# ICEBoard_rev1_0.net
KiCad netlist of a schematic drawn in Altium Designer
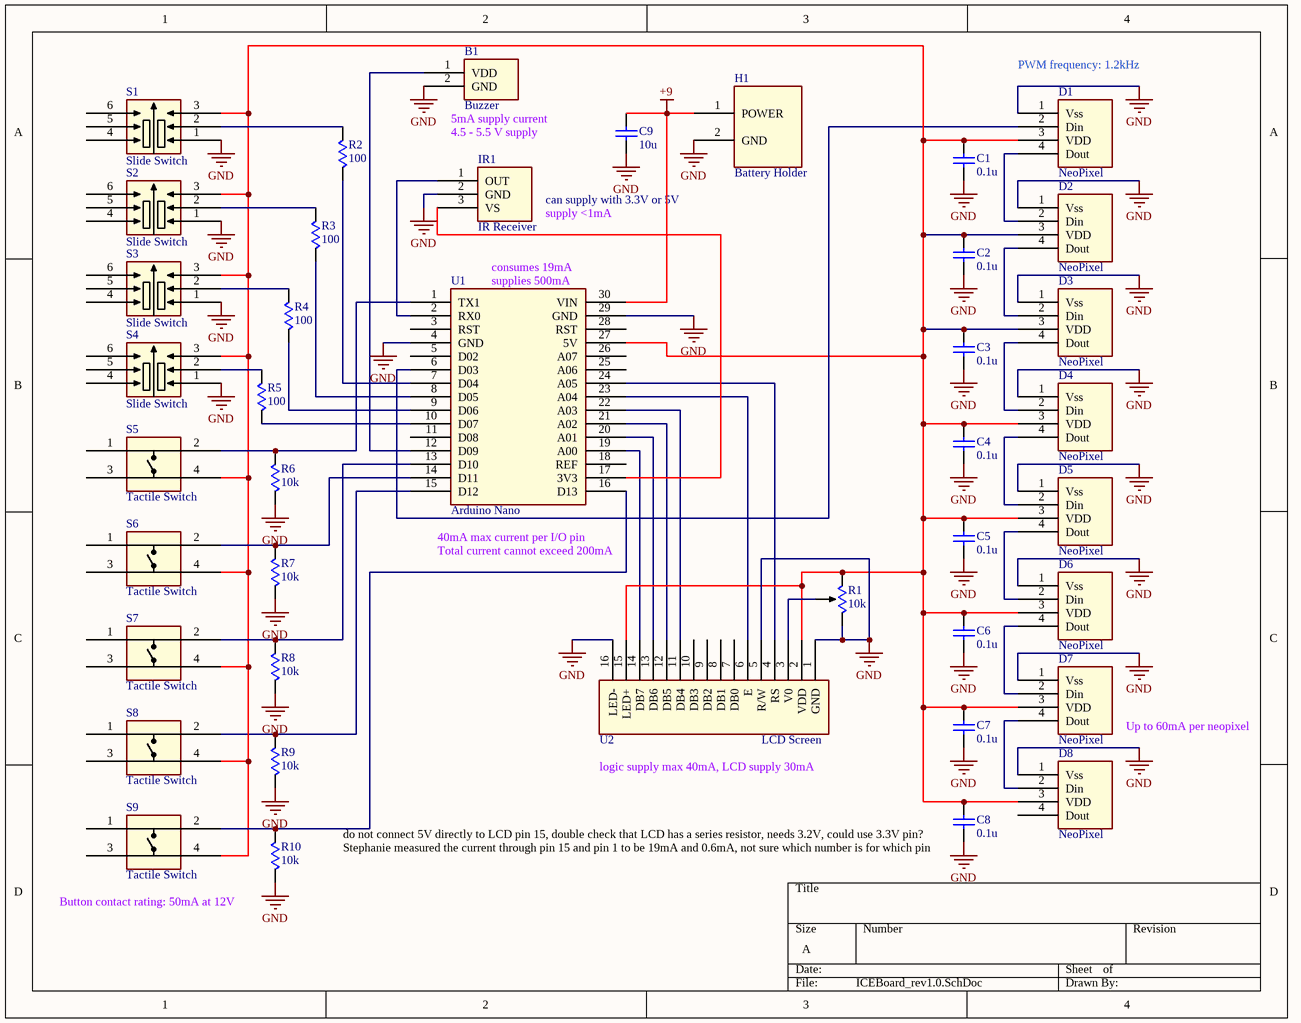
[diagram p0: ICEBoard_rev1.0.SchDoc]

(export (version "E")
  (design (tool "Eeschema 10.0.6"))
  (components
    (comp (ref "B1") (value "Buzzer") (footprint "TP124005") (libsource (lib "TP124005") (part "TP124005")))
    (comp (ref "C1") (value "0.1u") (footprint "Capacitor") (libsource (lib "Capacitor") (part "Capacitor")))
    (comp (ref "C2") (value "0.1u") (footprint "Capacitor") (libsource (lib "Capacitor") (part "Capacitor")))
    (comp (ref "C3") (value "0.1u") (footprint "Capacitor") (libsource (lib "Capacitor") (part "Capacitor")))
    (comp (ref "C4") (value "0.1u") (footprint "Capacitor") (libsource (lib "Capacitor") (part "Capacitor")))
    (comp (ref "C5") (value "0.1u") (footprint "Capacitor") (libsource (lib "Capacitor") (part "Capacitor")))
    (comp (ref "C6") (value "0.1u") (footprint "Capacitor") (libsource (lib "Capacitor") (part "Capacitor")))
    (comp (ref "C7") (value "0.1u") (footprint "Capacitor") (libsource (lib "Capacitor") (part "Capacitor")))
    (comp (ref "C8") (value "0.1u") (footprint "Capacitor") (libsource (lib "Capacitor") (part "Capacitor")))
    (comp (ref "C9")
      (value "10u")
      (footprint "PCBComponent_1")
      (libsource (lib "Capacitor") (part "Capacitor"))
    )
    (comp (ref "D1") (value "NeoPixel") (footprint "NeoPixel") (libsource (lib "NeoPixel") (part "NeoPixel")))
    (comp (ref "D2") (value "NeoPixel") (footprint "NeoPixel") (libsource (lib "NeoPixel") (part "NeoPixel")))
    (comp (ref "D3") (value "NeoPixel") (footprint "NeoPixel") (libsource (lib "NeoPixel") (part "NeoPixel")))
    (comp (ref "D4") (value "NeoPixel") (footprint "NeoPixel") (libsource (lib "NeoPixel") (part "NeoPixel")))
    (comp (ref "D5") (value "NeoPixel") (footprint "NeoPixel") (libsource (lib "NeoPixel") (part "NeoPixel")))
    (comp (ref "D6") (value "NeoPixel") (footprint "NeoPixel") (libsource (lib "NeoPixel") (part "NeoPixel")))
    (comp (ref "D7") (value "NeoPixel") (footprint "NeoPixel") (libsource (lib "NeoPixel") (part "NeoPixel")))
    (comp (ref "D8") (value "NeoPixel") (footprint "NeoPixel") (libsource (lib "NeoPixel") (part "NeoPixel")))
    (comp (ref "H1") (value "Battery Holder") (footprint "BH9VPC") (libsource (lib "BH9VPC") (part "BH9VPC")))
    (comp (ref "IR1")
      (value "IR Receiver")
      (footprint "TSOP382")
      (libsource (lib "TSOP382") (part "TSOP382"))
    )
    (comp (ref "R1")
      (value "10k")
      (footprint "TC33X")
      (libsource (lib "Resistor - Variable") (part "Resistor - Variable"))
    )
    (comp (ref "R2") (value "100") (footprint "Resistor1608") (libsource (lib "Resistor") (part "Resistor")))
    (comp (ref "R3") (value "100") (footprint "Resistor1608") (libsource (lib "Resistor") (part "Resistor")))
    (comp (ref "R4") (value "100") (footprint "Resistor1608") (libsource (lib "Resistor") (part "Resistor")))
    (comp (ref "R5") (value "100") (footprint "Resistor1608") (libsource (lib "Resistor") (part "Resistor")))
    (comp (ref "R6") (value "10k") (footprint "Resistor1608") (libsource (lib "Resistor") (part "Resistor")))
    (comp (ref "R7") (value "10k") (footprint "Resistor1608") (libsource (lib "Resistor") (part "Resistor")))
    (comp (ref "R8") (value "10k") (footprint "Resistor1608") (libsource (lib "Resistor") (part "Resistor")))
    (comp (ref "R9") (value "10k") (footprint "Resistor1608") (libsource (lib "Resistor") (part "Resistor")))
    (comp (ref "R10") (value "10k") (footprint "Resistor1608") (libsource (lib "Resistor") (part "Resistor")))
    (comp (ref "S1")
      (value "Slide Switch")
      (footprint "JS202011SCQN")
      (libsource (lib "JS202011SCQN") (part "JS202011SCQN"))
    )
    (comp (ref "S2")
      (value "Slide Switch")
      (footprint "JS202011SCQN")
      (libsource (lib "JS202011SCQN") (part "JS202011SCQN"))
    )
    (comp (ref "S3")
      (value "Slide Switch")
      (footprint "JS202011SCQN")
      (libsource (lib "JS202011SCQN") (part "JS202011SCQN"))
    )
    (comp (ref "S4")
      (value "Slide Switch")
      (footprint "JS202011SCQN")
      (libsource (lib "JS202011SCQN") (part "JS202011SCQN"))
    )
    (comp (ref "S5") (value "Tactile Switch") (footprint "PTS645") (libsource (lib "PTS645") (part "PTS645")))
    (comp (ref "S6") (value "Tactile Switch") (footprint "PTS645") (libsource (lib "PTS645") (part "PTS645")))
    (comp (ref "S7") (value "Tactile Switch") (footprint "PTS645") (libsource (lib "PTS645") (part "PTS645")))
    (comp (ref "S8") (value "Tactile Switch") (footprint "PTS645") (libsource (lib "PTS645") (part "PTS645")))
    (comp (ref "S9") (value "Tactile Switch") (footprint "PTS645") (libsource (lib "PTS645") (part "PTS645")))
    (comp (ref "U1")
      (value "Arduino Nano")
      (footprint "ArduinoNano")
      (libsource (lib "ArduinoNano") (part "ArduinoNano"))
    )
    (comp (ref "U2")
      (value "LCD Screen")
      (footprint "TC1602A-01T")
      (libsource (lib "TC1602A-01T") (part "TC1602A-01T"))
    )
  )
  (nets
    (net (code "1") (name "+9") (class "Default")
      (node (ref "C9") (pin "1") (pinfunction "1_1") (pintype "passive"))
      (node (ref "H1") (pin "1") (pinfunction "POWER_1") (pintype "passive"))
      (node (ref "U1") (pin "30") (pinfunction "VIN_30") (pintype "passive"))
    )
    (net (code "2") (name "GND") (class "Default")
      (node (ref "B1") (pin "2") (pinfunction "GND_2") (pintype "passive"))
      (node (ref "C1") (pin "2") (pinfunction "2_2") (pintype "passive"))
      (node (ref "C2") (pin "2") (pinfunction "2_2") (pintype "passive"))
      (node (ref "C3") (pin "2") (pinfunction "2_2") (pintype "passive"))
      (node (ref "C4") (pin "2") (pinfunction "2_2") (pintype "passive"))
      (node (ref "C5") (pin "2") (pinfunction "2_2") (pintype "passive"))
      (node (ref "C6") (pin "2") (pinfunction "2_2") (pintype "passive"))
      (node (ref "C7") (pin "2") (pinfunction "2_2") (pintype "passive"))
      (node (ref "C8") (pin "2") (pinfunction "2_2") (pintype "passive"))
      (node (ref "C9") (pin "2") (pinfunction "2_2") (pintype "passive"))
      (node (ref "D1") (pin "1") (pinfunction "Vss_1") (pintype "passive"))
      (node (ref "D2") (pin "1") (pinfunction "Vss_1") (pintype "passive"))
      (node (ref "D3") (pin "1") (pinfunction "Vss_1") (pintype "passive"))
      (node (ref "D4") (pin "1") (pinfunction "Vss_1") (pintype "passive"))
      (node (ref "D5") (pin "1") (pinfunction "Vss_1") (pintype "passive"))
      (node (ref "D6") (pin "1") (pinfunction "Vss_1") (pintype "passive"))
      (node (ref "D7") (pin "1") (pinfunction "Vss_1") (pintype "passive"))
      (node (ref "D8") (pin "1") (pinfunction "Vss_1") (pintype "passive"))
      (node (ref "H1") (pin "2") (pinfunction "GND_2") (pintype "passive"))
      (node (ref "IR1") (pin "2") (pinfunction "GND_2") (pintype "passive"))
      (node (ref "R1") (pin "1") (pinfunction "1_1") (pintype "passive"))
      (node (ref "R10") (pin "1") (pinfunction "1_1") (pintype "passive"))
      (node (ref "R6") (pin "1") (pinfunction "1_1") (pintype "passive"))
      (node (ref "R7") (pin "1") (pinfunction "1_1") (pintype "passive"))
      (node (ref "R8") (pin "1") (pinfunction "1_1") (pintype "passive"))
      (node (ref "R9") (pin "1") (pinfunction "1_1") (pintype "passive"))
      (node (ref "S1") (pin "1") (pintype "passive"))
      (node (ref "S2") (pin "1") (pintype "passive"))
      (node (ref "S3") (pin "1") (pintype "passive"))
      (node (ref "S4") (pin "1") (pintype "passive"))
      (node (ref "U1") (pin "29") (pinfunction "GND_29") (pintype "passive"))
      (node (ref "U1") (pin "4") (pinfunction "GND_4") (pintype "passive"))
      (node (ref "U2") (pin "1") (pinfunction "GND_1") (pintype "passive"))
      (node (ref "U2") (pin "16") (pinfunction "LED-_16") (pintype "passive"))
      (node (ref "U2") (pin "5") (pinfunction "R/W_5") (pintype "passive"))
    )
    (net (code "3") (name "Net-(B1-VDD)") (class "Default")
      (node (ref "B1") (pin "1") (pinfunction "VDD_1") (pintype "passive"))
      (node (ref "U1") (pin "12") (pinfunction "D09_12") (pintype "passive"))
    )
    (net (code "4") (name "Net-(D1-Din)") (class "Default")
      (node (ref "D1") (pin "2") (pinfunction "Din_2") (pintype "passive"))
      (node (ref "U1") (pin "6") (pinfunction "D03_6") (pintype "passive"))
    )
    (net (code "5") (name "Net-(D1-Dout)") (class "Default")
      (node (ref "D1") (pin "4") (pinfunction "Dout_4") (pintype "passive"))
      (node (ref "D2") (pin "2") (pinfunction "Din_2") (pintype "passive"))
    )
    (net (code "6") (name "Net-(D1-VDD)") (class "Default")
      (node (ref "C1") (pin "1") (pinfunction "1_1") (pintype "passive"))
      (node (ref "C2") (pin "1") (pinfunction "1_1") (pintype "passive"))
      (node (ref "C3") (pin "1") (pinfunction "1_1") (pintype "passive"))
      (node (ref "C4") (pin "1") (pinfunction "1_1") (pintype "passive"))
      (node (ref "C5") (pin "1") (pinfunction "1_1") (pintype "passive"))
      (node (ref "C6") (pin "1") (pinfunction "1_1") (pintype "passive"))
      (node (ref "C7") (pin "1") (pinfunction "1_1") (pintype "passive"))
      (node (ref "C8") (pin "1") (pinfunction "1_1") (pintype "passive"))
      (node (ref "D1") (pin "3") (pinfunction "VDD_3") (pintype "passive"))
      (node (ref "D2") (pin "3") (pinfunction "VDD_3") (pintype "passive"))
      (node (ref "D3") (pin "3") (pinfunction "VDD_3") (pintype "passive"))
      (node (ref "D4") (pin "3") (pinfunction "VDD_3") (pintype "passive"))
      (node (ref "D5") (pin "3") (pinfunction "VDD_3") (pintype "passive"))
      (node (ref "D6") (pin "3") (pinfunction "VDD_3") (pintype "passive"))
      (node (ref "D7") (pin "3") (pinfunction "VDD_3") (pintype "passive"))
      (node (ref "D8") (pin "3") (pinfunction "VDD_3") (pintype "passive"))
      (node (ref "R1") (pin "3") (pinfunction "3_3") (pintype "passive"))
      (node (ref "S1") (pin "3") (pintype "passive"))
      (node (ref "S2") (pin "3") (pintype "passive"))
      (node (ref "S3") (pin "3") (pintype "passive"))
      (node (ref "S4") (pin "3") (pintype "passive"))
      (node (ref "S5") (pin "4") (pintype "passive"))
      (node (ref "S6") (pin "4") (pintype "passive"))
      (node (ref "S7") (pin "4") (pintype "passive"))
      (node (ref "S8") (pin "4") (pintype "passive"))
      (node (ref "S9") (pin "4") (pintype "passive"))
      (node (ref "U1") (pin "27") (pinfunction "5V_27") (pintype "passive"))
      (node (ref "U2") (pin "15") (pinfunction "LED+_15") (pintype "passive"))
      (node (ref "U2") (pin "2") (pinfunction "VDD_2") (pintype "passive"))
    )
    (net (code "7") (name "Net-(D2-Dout)") (class "Default")
      (node (ref "D2") (pin "4") (pinfunction "Dout_4") (pintype "passive"))
      (node (ref "D3") (pin "2") (pinfunction "Din_2") (pintype "passive"))
    )
    (net (code "8") (name "Net-(D3-Dout)") (class "Default")
      (node (ref "D3") (pin "4") (pinfunction "Dout_4") (pintype "passive"))
      (node (ref "D4") (pin "2") (pinfunction "Din_2") (pintype "passive"))
    )
    (net (code "9") (name "Net-(D4-Dout)") (class "Default")
      (node (ref "D4") (pin "4") (pinfunction "Dout_4") (pintype "passive"))
      (node (ref "D5") (pin "2") (pinfunction "Din_2") (pintype "passive"))
    )
    (net (code "10") (name "Net-(D5-Dout)") (class "Default")
      (node (ref "D5") (pin "4") (pinfunction "Dout_4") (pintype "passive"))
      (node (ref "D6") (pin "2") (pinfunction "Din_2") (pintype "passive"))
    )
    (net (code "11") (name "Net-(D6-Dout)") (class "Default")
      (node (ref "D6") (pin "4") (pinfunction "Dout_4") (pintype "passive"))
      (node (ref "D7") (pin "2") (pinfunction "Din_2") (pintype "passive"))
    )
    (net (code "12") (name "Net-(D7-Dout)") (class "Default")
      (node (ref "D7") (pin "4") (pinfunction "Dout_4") (pintype "passive"))
      (node (ref "D8") (pin "2") (pinfunction "Din_2") (pintype "passive"))
    )
    (net (code "13") (name "Net-(IR1-OUT)") (class "Default")
      (node (ref "IR1") (pin "1") (pinfunction "OUT_1") (pintype "passive"))
      (node (ref "U1") (pin "2") (pinfunction "RX0_2") (pintype "passive"))
    )
    (net (code "14") (name "Net-(IR1-VS)") (class "Default")
      (node (ref "IR1") (pin "3") (pinfunction "VS_3") (pintype "passive"))
      (node (ref "U1") (pin "17") (pinfunction "3V3_17") (pintype "passive"))
    )
    (net (code "15") (name "Net-(R2-Pad2)") (class "Default")
      (node (ref "R2") (pin "2") (pinfunction "2_2") (pintype "passive"))
      (node (ref "S1") (pin "2") (pintype "passive"))
    )
    (net (code "16") (name "Net-(R3-Pad2)") (class "Default")
      (node (ref "R3") (pin "2") (pinfunction "2_2") (pintype "passive"))
      (node (ref "S2") (pin "2") (pintype "passive"))
    )
    (net (code "17") (name "Net-(R4-Pad2)") (class "Default")
      (node (ref "R4") (pin "2") (pinfunction "2_2") (pintype "passive"))
      (node (ref "S3") (pin "2") (pintype "passive"))
    )
    (net (code "18") (name "Net-(R5-Pad2)") (class "Default")
      (node (ref "R5") (pin "2") (pinfunction "2_2") (pintype "passive"))
      (node (ref "S4") (pin "2") (pintype "passive"))
    )
    (net (code "19") (name "Net-(U1-A00)") (class "Default")
      (node (ref "U1") (pin "19") (pinfunction "A00_19") (pintype "passive"))
      (node (ref "U2") (pin "14") (pinfunction "DB7_14") (pintype "passive"))
    )
    (net (code "20") (name "Net-(U1-A01)") (class "Default")
      (node (ref "U1") (pin "20") (pinfunction "A01_20") (pintype "passive"))
      (node (ref "U2") (pin "13") (pinfunction "DB6_13") (pintype "passive"))
    )
    (net (code "21") (name "Net-(U1-A02)") (class "Default")
      (node (ref "U1") (pin "21") (pinfunction "A02_21") (pintype "passive"))
      (node (ref "U2") (pin "12") (pinfunction "DB5_12") (pintype "passive"))
    )
    (net (code "22") (name "Net-(U1-A03)") (class "Default")
      (node (ref "U1") (pin "22") (pinfunction "A03_22") (pintype "passive"))
      (node (ref "U2") (pin "11") (pinfunction "DB4_11") (pintype "passive"))
    )
    (net (code "23") (name "Net-(U1-A04)") (class "Default")
      (node (ref "U1") (pin "23") (pinfunction "A04_23") (pintype "passive"))
      (node (ref "U2") (pin "6") (pinfunction "E_6") (pintype "passive"))
    )
    (net (code "24") (name "Net-(U1-A05)") (class "Default")
      (node (ref "U1") (pin "24") (pinfunction "A05_24") (pintype "passive"))
      (node (ref "U2") (pin "4") (pinfunction "RS_4") (pintype "passive"))
    )
    (net (code "25") (name "Net-(U1-D04)") (class "Default")
      (node (ref "R2") (pin "1") (pinfunction "1_1") (pintype "passive"))
      (node (ref "U1") (pin "7") (pinfunction "D04_7") (pintype "passive"))
    )
    (net (code "26") (name "Net-(U1-D05)") (class "Default")
      (node (ref "R3") (pin "1") (pinfunction "1_1") (pintype "passive"))
      (node (ref "U1") (pin "8") (pinfunction "D05_8") (pintype "passive"))
    )
    (net (code "27") (name "Net-(U1-D06)") (class "Default")
      (node (ref "R4") (pin "1") (pinfunction "1_1") (pintype "passive"))
      (node (ref "U1") (pin "9") (pinfunction "D06_9") (pintype "passive"))
    )
    (net (code "28") (name "Net-(U1-D07)") (class "Default")
      (node (ref "R5") (pin "1") (pinfunction "1_1") (pintype "passive"))
      (node (ref "U1") (pin "10") (pinfunction "D07_10") (pintype "passive"))
    )
    (net (code "29") (name "Net-(U1-D10)") (class "Default")
      (node (ref "R8") (pin "2") (pinfunction "2_2") (pintype "passive"))
      (node (ref "S7") (pin "2") (pintype "passive"))
      (node (ref "U1") (pin "13") (pinfunction "D10_13") (pintype "passive"))
    )
    (net (code "30") (name "Net-(U1-D11)") (class "Default")
      (node (ref "R7") (pin "2") (pinfunction "2_2") (pintype "passive"))
      (node (ref "S6") (pin "2") (pintype "passive"))
      (node (ref "U1") (pin "14") (pinfunction "D11_14") (pintype "passive"))
    )
    (net (code "31") (name "Net-(U1-D12)") (class "Default")
      (node (ref "R9") (pin "2") (pinfunction "2_2") (pintype "passive"))
      (node (ref "S8") (pin "2") (pintype "passive"))
      (node (ref "U1") (pin "15") (pinfunction "D12_15") (pintype "passive"))
    )
    (net (code "32") (name "Net-(U1-D13)") (class "Default")
      (node (ref "R10") (pin "2") (pinfunction "2_2") (pintype "passive"))
      (node (ref "S9") (pin "2") (pintype "passive"))
      (node (ref "U1") (pin "16") (pinfunction "D13_16") (pintype "passive"))
    )
    (net (code "33") (name "Net-(U1-TX1)") (class "Default")
      (node (ref "R6") (pin "2") (pinfunction "2_2") (pintype "passive"))
      (node (ref "S5") (pin "2") (pintype "passive"))
      (node (ref "U1") (pin "1") (pinfunction "TX1_1") (pintype "passive"))
    )
    (net (code "34") (name "Net-(U2-V0)") (class "Default")
      (node (ref "R1") (pin "2") (pinfunction "2_2") (pintype "passive"))
      (node (ref "U2") (pin "3") (pinfunction "V0_3") (pintype "passive"))
    )
    (net (code "35") (name "unconnected-(D8-Dout-Pad4)") (class "Default")
      (node (ref "D8") (pin "4") (pinfunction "Dout_4") (pintype "passive"))
    )
    (net (code "36") (name "unconnected-(S1-Pad4)") (class "Default")
      (node (ref "S1") (pin "4") (pintype "passive"))
    )
    (net (code "37") (name "unconnected-(S1-Pad5)") (class "Default")
      (node (ref "S1") (pin "5") (pintype "passive"))
    )
    (net (code "38") (name "unconnected-(S1-Pad6)") (class "Default")
      (node (ref "S1") (pin "6") (pintype "passive"))
    )
    (net (code "39") (name "unconnected-(S2-Pad4)") (class "Default")
      (node (ref "S2") (pin "4") (pintype "passive"))
    )
    (net (code "40") (name "unconnected-(S2-Pad5)") (class "Default")
      (node (ref "S2") (pin "5") (pintype "passive"))
    )
    (net (code "41") (name "unconnected-(S2-Pad6)") (class "Default")
      (node (ref "S2") (pin "6") (pintype "passive"))
    )
    (net (code "42") (name "unconnected-(S3-Pad4)") (class "Default")
      (node (ref "S3") (pin "4") (pintype "passive"))
    )
    (net (code "43") (name "unconnected-(S3-Pad5)") (class "Default")
      (node (ref "S3") (pin "5") (pintype "passive"))
    )
    (net (code "44") (name "unconnected-(S3-Pad6)") (class "Default")
      (node (ref "S3") (pin "6") (pintype "passive"))
    )
    (net (code "45") (name "unconnected-(S4-Pad4)") (class "Default")
      (node (ref "S4") (pin "4") (pintype "passive"))
    )
    (net (code "46") (name "unconnected-(S4-Pad5)") (class "Default")
      (node (ref "S4") (pin "5") (pintype "passive"))
    )
    (net (code "47") (name "unconnected-(S4-Pad6)") (class "Default")
      (node (ref "S4") (pin "6") (pintype "passive"))
    )
    (net (code "48") (name "unconnected-(S5-Pad1)") (class "Default")
      (node (ref "S5") (pin "1") (pintype "passive"))
    )
    (net (code "49") (name "unconnected-(S5-Pad3)") (class "Default")
      (node (ref "S5") (pin "3") (pintype "passive"))
    )
    (net (code "50") (name "unconnected-(S6-Pad1)") (class "Default")
      (node (ref "S6") (pin "1") (pintype "passive"))
    )
    (net (code "51") (name "unconnected-(S6-Pad3)") (class "Default")
      (node (ref "S6") (pin "3") (pintype "passive"))
    )
    (net (code "52") (name "unconnected-(S7-Pad1)") (class "Default")
      (node (ref "S7") (pin "1") (pintype "passive"))
    )
    (net (code "53") (name "unconnected-(S7-Pad3)") (class "Default")
      (node (ref "S7") (pin "3") (pintype "passive"))
    )
    (net (code "54") (name "unconnected-(S8-Pad1)") (class "Default")
      (node (ref "S8") (pin "1") (pintype "passive"))
    )
    (net (code "55") (name "unconnected-(S8-Pad3)") (class "Default")
      (node (ref "S8") (pin "3") (pintype "passive"))
    )
    (net (code "56") (name "unconnected-(S9-Pad1)") (class "Default")
      (node (ref "S9") (pin "1") (pintype "passive"))
    )
    (net (code "57") (name "unconnected-(S9-Pad3)") (class "Default")
      (node (ref "S9") (pin "3") (pintype "passive"))
    )
    (net (code "58") (name "unconnected-(U1-A06-Pad25)") (class "Default")
      (node (ref "U1") (pin "25") (pinfunction "A06_25") (pintype "passive"))
    )
    (net (code "59") (name "unconnected-(U1-A07-Pad26)") (class "Default")
      (node (ref "U1") (pin "26") (pinfunction "A07_26") (pintype "passive"))
    )
    (net (code "60") (name "unconnected-(U1-D02-Pad5)") (class "Default")
      (node (ref "U1") (pin "5") (pinfunction "D02_5") (pintype "passive"))
    )
    (net (code "61") (name "unconnected-(U1-D08-Pad11)") (class "Default")
      (node (ref "U1") (pin "11") (pinfunction "D08_11") (pintype "passive"))
    )
    (net (code "62") (name "unconnected-(U1-REF-Pad18)") (class "Default")
      (node (ref "U1") (pin "18") (pinfunction "REF_18") (pintype "passive"))
    )
    (net (code "63") (name "unconnected-(U1-RST-Pad3)") (class "Default")
      (node (ref "U1") (pin "3") (pinfunction "RST_3") (pintype "passive"))
    )
    (net (code "64") (name "unconnected-(U1-RST-Pad28)") (class "Default")
      (node (ref "U1") (pin "28") (pinfunction "RST_28") (pintype "passive"))
    )
    (net (code "65") (name "unconnected-(U2-DB0-Pad7)") (class "Default")
      (node (ref "U2") (pin "7") (pinfunction "DB0_7") (pintype "passive"))
    )
    (net (code "66") (name "unconnected-(U2-DB1-Pad8)") (class "Default")
      (node (ref "U2") (pin "8") (pinfunction "DB1_8") (pintype "passive"))
    )
    (net (code "67") (name "unconnected-(U2-DB2-Pad9)") (class "Default")
      (node (ref "U2") (pin "9") (pinfunction "DB2_9") (pintype "passive"))
    )
    (net (code "68") (name "unconnected-(U2-DB3-Pad10)") (class "Default")
      (node (ref "U2") (pin "10") (pinfunction "DB3_10") (pintype "passive"))
    )
  )
)
